# PG3_SHEET1.net
KiCad netlist of a schematic drawn in Altium Designer
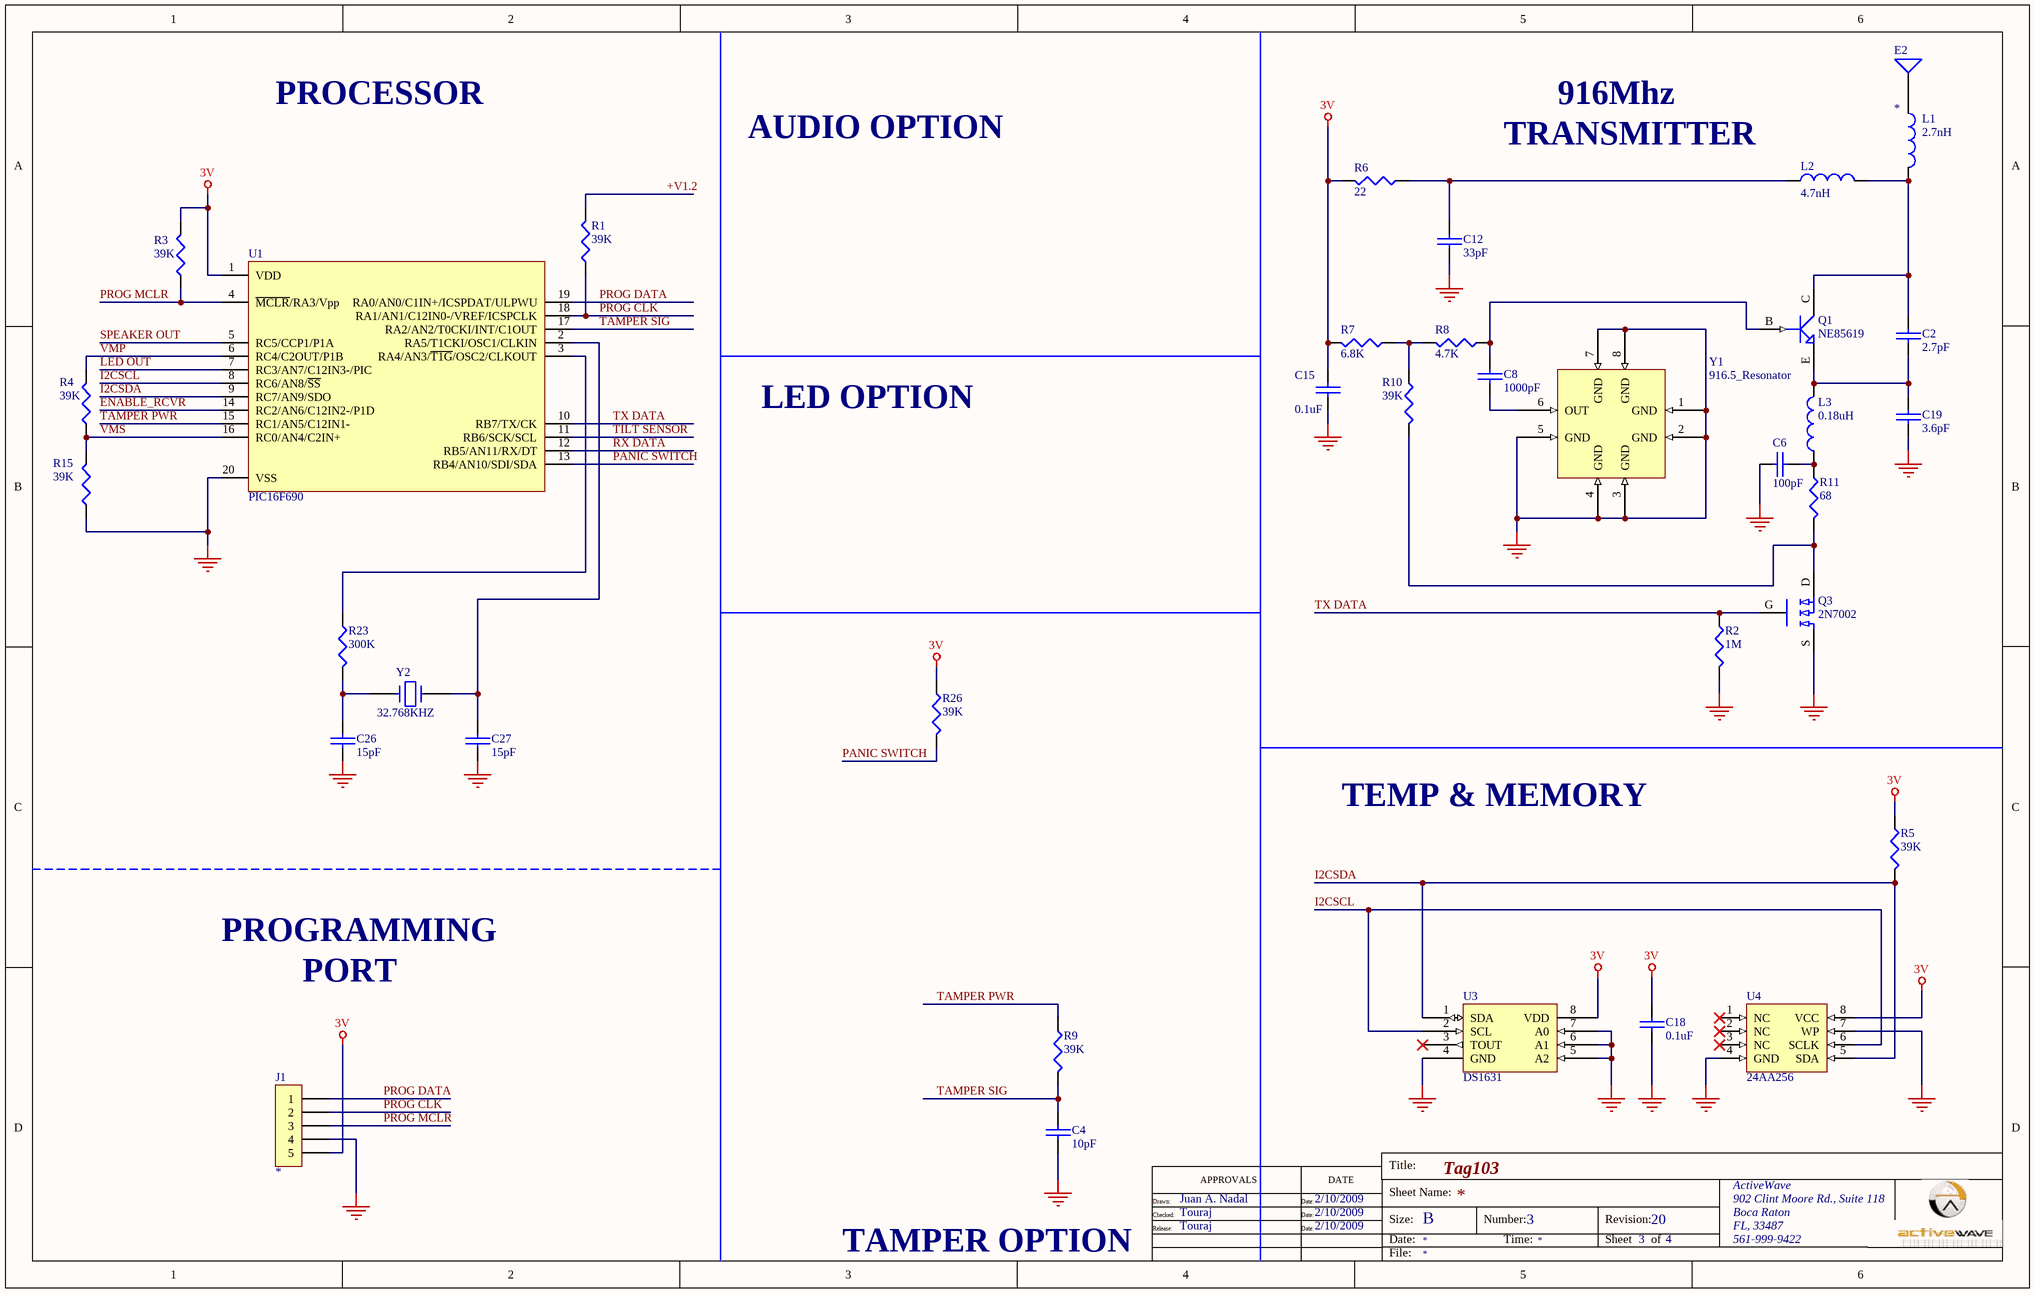
[diagram p0: PG3 SHEET1.schdoc]

(export (version "E")
  (design (tool "Eeschema 10.0.6"))
  (components
    (comp (ref "C2")
      (value "2.7pF")
      (footprint "0603")
      (description "Capacitor")
      (fields (field (name "Comment") "2 PF"))
      (libsource (lib "ActiveWave MasterLib") (part "CAP-0603"))
    )
    (comp (ref "C4")
      (value "10pF")
      (footprint "0603")
      (description "Capacitor")
      (libsource (lib "ActiveWave MasterLib") (part "CAP-0603"))
    )
    (comp (ref "C6")
      (value "100pF")
      (footprint "0603")
      (description "Capacitor")
      (fields (field (name "Comment") "100 pF"))
      (libsource (lib "ActiveWave MasterLib") (part "CAP-0603"))
    )
    (comp (ref "C8")
      (value "1000pF")
      (footprint "0603")
      (description "Capacitor")
      (fields (field (name "Comment") "1000 pF"))
      (libsource (lib "ActiveWave MasterLib") (part "CAP-0603"))
    )
    (comp (ref "C12")
      (value "33pF")
      (footprint "0603")
      (description "Capacitor")
      (fields (field (name "Comment") "33 pF"))
      (libsource (lib "ActiveWave MasterLib") (part "CAP-0603"))
    )
    (comp (ref "C15")
      (value "0.1uF")
      (footprint "0603")
      (description "Capacitor")
      (fields (field (name "Comment") "0.1 uF"))
      (libsource (lib "ActiveWave MasterLib") (part "CAP-0603"))
    )
    (comp (ref "C18")
      (value "0.1uF")
      (footprint "0603")
      (description "Capacitor")
      (fields (field (name "Comment") "0.1 uF"))
      (libsource (lib "ActiveWave MasterLib") (part "CAP-0603"))
    )
    (comp (ref "C19")
      (value "3.6pF")
      (footprint "0603")
      (description "Capacitor")
      (fields (field (name "Comment") "2.7 pF"))
      (libsource (lib "ActiveWave MasterLib") (part "CAP-0603"))
    )
    (comp (ref "C26")
      (value "15pF")
      (footprint "0603")
      (description "Capacitor")
      (libsource (lib "ActiveWave MasterLib") (part "CAP-0603"))
    )
    (comp (ref "C27")
      (value "15pF")
      (footprint "0603")
      (description "Capacitor")
      (libsource (lib "ActiveWave MasterLib") (part "CAP-0603"))
    )
    (comp (ref "E2")
      (value "*")
      (footprint "Antenna1")
      (fields (field (name "PART-VALUE") "*"))
      (libsource (lib "ActiveWave MasterLib") (part "Antenna1"))
    )
    (comp (ref "J1")
      (value "1X5 HEADER")
      (footprint "CONN5")
      (description "Connector")
      (fields (field (name "PART-VALUE") "*"))
      (libsource (lib "ActiveWave MasterLib") (part "CON5"))
    )
    (comp (ref "L1")
      (value "2.7nH")
      (footprint "0603")
      (libsource (lib "ActiveWave MasterLib") (part "INDUCTOR"))
    )
    (comp (ref "L2")
      (value "4.7nH")
      (footprint "0603")
      (fields (field (name "Comment") "10nH"))
      (libsource (lib "ActiveWave MasterLib") (part "INDUCTOR"))
    )
    (comp (ref "L3")
      (value "0.18uH")
      (footprint "0603")
      (libsource (lib "ActiveWave MasterLib") (part "INDUCTOR"))
    )
    (comp (ref "Q1")
      (value "NE85619")
      (footprint "3 PIN ULTRA SUPER MINI MOLD")
      (description "NPN Transistor")
      (libsource (lib "ActiveWave MasterLib") (part "NE85619"))
    )
    (comp (ref "Q3")
      (value "2N7002")
      (footprint "SOT23 FET")
      (libsource (lib "ActiveWave MasterLib") (part "2N7002"))
    )
    (comp (ref "R1")
      (value "39K")
      (footprint "0603")
      (libsource (lib "ActiveWave MasterLib") (part "RES-0603"))
    )
    (comp (ref "R2")
      (value "1M")
      (fields (field (name "Comment") "1 M"))
      (libsource (lib "ActiveWave MasterLib") (part "RES-0402"))
    )
    (comp (ref "R3")
      (value "39K")
      (footprint "0603")
      (libsource (lib "ActiveWave MasterLib") (part "RES-0603"))
    )
    (comp (ref "R4")
      (value "39K")
      (footprint "0603")
      (libsource (lib "ActiveWave MasterLib") (part "RES-0603"))
    )
    (comp (ref "R5")
      (value "39K")
      (footprint "0603")
      (libsource (lib "ActiveWave MasterLib") (part "RES-0603"))
    )
    (comp (ref "R6") (value "22") (libsource (lib "ActiveWave MasterLib") (part "RES-0402")))
    (comp (ref "R7") (value "6.8K") (libsource (lib "ActiveWave MasterLib") (part "RES-0402")))
    (comp (ref "R8")
      (value "4.7K")
      (fields (field (name "Comment") "4.7 K"))
      (libsource (lib "ActiveWave MasterLib") (part "RES-0402"))
    )
    (comp (ref "R9")
      (value "39K")
      (footprint "0603")
      (libsource (lib "ActiveWave MasterLib") (part "RES-0603"))
    )
    (comp (ref "R10")
      (value "39K")
      (footprint "0603")
      (libsource (lib "ActiveWave MasterLib") (part "RES-0603"))
    )
    (comp (ref "R11") (value "68") (libsource (lib "ActiveWave MasterLib") (part "RES-0402")))
    (comp (ref "R15")
      (value "39K")
      (footprint "0603")
      (libsource (lib "ActiveWave MasterLib") (part "RES-0603"))
    )
    (comp (ref "R23")
      (value "300K")
      (footprint "0603")
      (libsource (lib "ActiveWave MasterLib") (part "RES-0603"))
    )
    (comp (ref "R26")
      (value "39K")
      (footprint "0603")
      (fields (field (name "Comment") "4.7M"))
      (libsource (lib "ActiveWave MasterLib") (part "RES-0603"))
    )
    (comp (ref "U1")
      (value "PIC16F690")
      (footprint "SSOP20 WIDE")
      (libsource (lib "ActiveWave MasterLib") (part "PIC16F690"))
    )
    (comp (ref "U3")
      (value "DS1631")
      (footprint "SO8 SMALL")
      (libsource (lib "ActiveWave MasterLib") (part "DS1631"))
    )
    (comp (ref "U4")
      (value "24AA256")
      (footprint "SO8")
      (libsource (lib "ActiveWave MasterLib") (part "24AA256"))
    )
    (comp (ref "Y1")
      (value "916.5_Resonator")
      (footprint "RESONATOR")
      (libsource (lib "ActiveWave MasterLib") (part "RESONATOR"))
    )
    (comp (ref "Y2")
      (value "32.768KHZ")
      (footprint "CRYSTAL ABRACON ABS07")
      (description "Crystal")
      (fields (field (name "Comment") "32.768KHZ CRYSTAL"))
      (libsource (lib "ActiveWave MasterLib") (part "CRYSTAL"))
    )
  )
  (nets
    (net (code "1") (name "/+V1.2") (class "Default")
      (node (ref "R1") (pin "2") (pinfunction "2_2") (pintype "passive"))
    )
    (net (code "2") (name "/ENABLE_RCVR") (class "Default")
      (node (ref "U1") (pin "14") (pinfunction "RC2/AN6/C12IN2-/P1D_14") (pintype "passive"))
    )
    (net (code "3") (name "/I2CSCL") (class "Default")
      (node (ref "U1") (pin "8") (pinfunction "RC6/AN8/~{SS}_8") (pintype "passive"))
      (node (ref "U3") (pin "2") (pinfunction "SCL_2") (pintype "input"))
      (node (ref "U4") (pin "6") (pinfunction "SCLK_6") (pintype "input"))
    )
    (net (code "4") (name "/I2CSDA") (class "Default")
      (node (ref "R5") (pin "2") (pinfunction "2_2") (pintype "passive"))
      (node (ref "U1") (pin "9") (pinfunction "RC7/AN9/SDO_9") (pintype "passive"))
      (node (ref "U3") (pin "1") (pinfunction "SDA_1") (pintype "bidirectional"))
      (node (ref "U4") (pin "5") (pinfunction "SDA_5") (pintype "input"))
    )
    (net (code "5") (name "/LED OUT") (class "Default")
      (node (ref "U1") (pin "7") (pinfunction "RC3/AN7/C12IN3-/PIC_7") (pintype "passive"))
    )
    (net (code "6") (name "/PANIC SWITCH") (class "Default")
      (node (ref "R26") (pin "2") (pinfunction "2_2") (pintype "passive"))
      (node (ref "U1") (pin "13") (pinfunction "RB4/AN10/SDI/SDA_13") (pintype "passive"))
    )
    (net (code "7") (name "/PROG CLK") (class "Default")
      (node (ref "J1") (pin "2") (pinfunction "2_2") (pintype "passive"))
      (node (ref "R1") (pin "1") (pinfunction "1_1") (pintype "passive"))
      (node (ref "U1") (pin "18") (pinfunction "RA1/AN1/C12IN0-/VREF/ICSPCLK_18") (pintype "passive"))
    )
    (net (code "8") (name "/PROG DATA") (class "Default")
      (node (ref "J1") (pin "1") (pinfunction "1_1") (pintype "passive"))
      (node (ref "U1") (pin "19") (pinfunction "RA0/AN0/C1IN+/ICSPDAT/ULPWU_19") (pintype "passive"))
    )
    (net (code "9") (name "/PROG MCLR") (class "Default")
      (node (ref "J1") (pin "3") (pinfunction "3_3") (pintype "passive"))
      (node (ref "R3") (pin "1") (pinfunction "1_1") (pintype "passive"))
      (node (ref "U1") (pin "4") (pinfunction "~{MCLR}/RA3/Vpp_4") (pintype "passive"))
    )
    (net (code "10") (name "/RX DATA") (class "Default")
      (node (ref "U1") (pin "12") (pinfunction "RB5/AN11/RX/DT_12") (pintype "passive"))
    )
    (net (code "11") (name "/SPEAKER OUT") (class "Default")
      (node (ref "U1") (pin "5") (pinfunction "RC5/CCP1/P1A_5") (pintype "passive"))
    )
    (net (code "12") (name "/TAMPER PWR") (class "Default")
      (node (ref "R9") (pin "1") (pinfunction "1_1") (pintype "passive"))
      (node (ref "U1") (pin "15") (pinfunction "RC1/AN5/C12IN1-_15") (pintype "passive"))
    )
    (net (code "13") (name "/TAMPER SIG") (class "Default")
      (node (ref "C4") (pin "1") (pinfunction "1_1") (pintype "passive"))
      (node (ref "R9") (pin "2") (pinfunction "2_2") (pintype "passive"))
      (node (ref "U1") (pin "17") (pinfunction "RA2/AN2/T0CKI/INT/C1OUT_17") (pintype "passive"))
    )
    (net (code "14") (name "/TILT SENSOR") (class "Default")
      (node (ref "U1") (pin "11") (pinfunction "RB6/SCK/SCL_11") (pintype "passive"))
    )
    (net (code "15") (name "/TX DATA") (class "Default")
      (node (ref "Q3") (pin "G") (pinfunction "G_G") (pintype "passive"))
      (node (ref "R2") (pin "1") (pinfunction "1_1") (pintype "passive"))
      (node (ref "U1") (pin "10") (pinfunction "RB7/TX/CK_10") (pintype "passive"))
    )
    (net (code "16") (name "/VMP") (class "Default")
      (node (ref "R4") (pin "2") (pinfunction "2_2") (pintype "passive"))
      (node (ref "U1") (pin "6") (pinfunction "RC4/C2OUT/P1B_6") (pintype "passive"))
    )
    (net (code "17") (name "/VMS") (class "Default")
      (node (ref "R15") (pin "2") (pinfunction "2_2") (pintype "passive"))
      (node (ref "R4") (pin "1") (pinfunction "1_1") (pintype "passive"))
      (node (ref "U1") (pin "16") (pinfunction "RC0/AN4/C2IN+_16") (pintype "passive"))
    )
    (net (code "18") (name "3V") (class "Default")
      (node (ref "C15") (pin "1") (pinfunction "1_1") (pintype "passive"))
      (node (ref "C18") (pin "1") (pinfunction "1_1") (pintype "passive"))
      (node (ref "J1") (pin "5") (pinfunction "5_5") (pintype "passive"))
      (node (ref "R26") (pin "1") (pinfunction "1_1") (pintype "passive"))
      (node (ref "R3") (pin "2") (pinfunction "2_2") (pintype "passive"))
      (node (ref "R5") (pin "1") (pinfunction "1_1") (pintype "passive"))
      (node (ref "R6") (pin "2") (pinfunction "2_2") (pintype "passive"))
      (node (ref "R7") (pin "2") (pinfunction "2_2") (pintype "passive"))
      (node (ref "U1") (pin "1") (pinfunction "VDD_1") (pintype "passive"))
      (node (ref "U3") (pin "8") (pinfunction "VDD_8") (pintype "power_in"))
      (node (ref "U4") (pin "8") (pinfunction "VCC_8") (pintype "input"))
    )
    (net (code "19") (name "GND") (class "Default")
      (node (ref "C12") (pin "2") (pinfunction "2_2") (pintype "passive"))
      (node (ref "C15") (pin "2") (pinfunction "2_2") (pintype "passive"))
      (node (ref "C18") (pin "2") (pinfunction "2_2") (pintype "passive"))
      (node (ref "C19") (pin "2") (pinfunction "2_2") (pintype "passive"))
      (node (ref "C26") (pin "2") (pinfunction "2_2") (pintype "passive"))
      (node (ref "C27") (pin "2") (pinfunction "2_2") (pintype "passive"))
      (node (ref "C4") (pin "2") (pinfunction "2_2") (pintype "passive"))
      (node (ref "C6") (pin "2") (pinfunction "2_2") (pintype "passive"))
      (node (ref "J1") (pin "4") (pinfunction "4_4") (pintype "passive"))
      (node (ref "Q3") (pin "S") (pinfunction "S_S") (pintype "passive"))
      (node (ref "R15") (pin "1") (pinfunction "1_1") (pintype "passive"))
      (node (ref "R2") (pin "2") (pinfunction "2_2") (pintype "passive"))
      (node (ref "U1") (pin "20") (pinfunction "VSS_20") (pintype "passive"))
      (node (ref "U3") (pin "4") (pinfunction "GND_4") (pintype "power_in"))
      (node (ref "U3") (pin "5") (pinfunction "A2_5") (pintype "input"))
      (node (ref "U3") (pin "6") (pinfunction "A1_6") (pintype "input"))
      (node (ref "U3") (pin "7") (pinfunction "A0_7") (pintype "input"))
      (node (ref "U4") (pin "4") (pinfunction "GND_4") (pintype "input"))
      (node (ref "U4") (pin "7") (pinfunction "WP_7") (pintype "input"))
      (node (ref "Y1") (pin "1") (pinfunction "GND_1") (pintype "input"))
      (node (ref "Y1") (pin "2") (pinfunction "GND_2") (pintype "input"))
      (node (ref "Y1") (pin "3") (pinfunction "GND_3") (pintype "input"))
      (node (ref "Y1") (pin "4") (pinfunction "GND_4") (pintype "input"))
      (node (ref "Y1") (pin "5") (pinfunction "GND_5") (pintype "input"))
      (node (ref "Y1") (pin "7") (pinfunction "GND_7") (pintype "input"))
      (node (ref "Y1") (pin "8") (pinfunction "GND_8") (pintype "input"))
    )
    (net (code "20") (name "Net-(C2-Pad1)") (class "Default")
      (node (ref "C2") (pin "1") (pinfunction "1_1") (pintype "passive"))
      (node (ref "L1") (pin "2") (pinfunction "2_2") (pintype "passive"))
      (node (ref "L2") (pin "2") (pinfunction "2_2") (pintype "passive"))
      (node (ref "Q1") (pin "C") (pinfunction "C_C") (pintype "passive"))
    )
    (net (code "21") (name "Net-(C6-Pad1)") (class "Default")
      (node (ref "C6") (pin "1") (pinfunction "1_1") (pintype "passive"))
      (node (ref "L3") (pin "1") (pinfunction "1_1") (pintype "passive"))
      (node (ref "R11") (pin "1") (pinfunction "1_1") (pintype "passive"))
    )
    (net (code "22") (name "Net-(C8-Pad1)") (class "Default")
      (node (ref "C8") (pin "1") (pinfunction "1_1") (pintype "passive"))
      (node (ref "Q1") (pin "B") (pinfunction "B_B") (pintype "input"))
      (node (ref "R8") (pin "1") (pinfunction "1_1") (pintype "passive"))
    )
    (net (code "23") (name "Net-(C12-Pad1)") (class "Default")
      (node (ref "C12") (pin "1") (pinfunction "1_1") (pintype "passive"))
      (node (ref "L2") (pin "1") (pinfunction "1_1") (pintype "passive"))
      (node (ref "R6") (pin "1") (pinfunction "1_1") (pintype "passive"))
    )
    (net (code "24") (name "Net-(C19-Pad1)") (class "Default")
      (node (ref "C19") (pin "1") (pinfunction "1_1") (pintype "passive"))
      (node (ref "C2") (pin "2") (pinfunction "2_2") (pintype "passive"))
      (node (ref "L3") (pin "2") (pinfunction "2_2") (pintype "passive"))
      (node (ref "Q1") (pin "E") (pinfunction "E_E") (pintype "passive"))
    )
    (net (code "25") (name "Net-(C26-Pad1)") (class "Default")
      (node (ref "C26") (pin "1") (pinfunction "1_1") (pintype "passive"))
      (node (ref "R23") (pin "2") (pinfunction "2_2") (pintype "passive"))
      (node (ref "Y2") (pin "1") (pinfunction "1_1") (pintype "passive"))
    )
    (net (code "26") (name "Net-(E2-Pad1)") (class "Default")
      (node (ref "E2") (pin "1") (pinfunction "1_1") (pintype "passive"))
      (node (ref "L1") (pin "1") (pinfunction "1_1") (pintype "passive"))
    )
    (net (code "27") (name "Net-(Q3-PadD)") (class "Default")
      (node (ref "Q3") (pin "D") (pinfunction "D_D") (pintype "passive"))
      (node (ref "R10") (pin "2") (pinfunction "2_2") (pintype "passive"))
      (node (ref "R11") (pin "2") (pinfunction "2_2") (pintype "passive"))
    )
    (net (code "28") (name "Net-(R10-Pad1)") (class "Default")
      (node (ref "R10") (pin "1") (pinfunction "1_1") (pintype "passive"))
      (node (ref "R7") (pin "1") (pinfunction "1_1") (pintype "passive"))
      (node (ref "R8") (pin "2") (pinfunction "2_2") (pintype "passive"))
    )
    (net (code "29") (name "Net-(U1-RA4{slash}AN3{slash}~{T1G}{slash}OSC2{slash}CLKOUT)") (class "Default")
      (node (ref "R23") (pin "1") (pinfunction "1_1") (pintype "passive"))
      (node (ref "U1") (pin "3") (pinfunction "RA4/AN3/~{T1G}/OSC2/CLKOUT_3") (pintype "passive"))
    )
    (net (code "30") (name "Net-(U1-RA5{slash}T1CKI{slash}OSC1{slash}CLKIN)") (class "Default")
      (node (ref "C27") (pin "1") (pinfunction "1_1") (pintype "passive"))
      (node (ref "U1") (pin "2") (pinfunction "RA5/T1CKI/OSC1/CLKIN_2") (pintype "passive"))
      (node (ref "Y2") (pin "2") (pinfunction "2_2") (pintype "passive"))
    )
    (net (code "31") (name "Net-(Y1-OUT)") (class "Default")
      (node (ref "C8") (pin "2") (pinfunction "2_2") (pintype "passive"))
      (node (ref "Y1") (pin "6") (pinfunction "OUT_6") (pintype "input"))
    )
    (net (code "32") (name "unconnected-(U3-TOUT-Pad3)") (class "Default")
      (node (ref "U3") (pin "3") (pinfunction "TOUT_3") (pintype "output+no_connect"))
    )
    (net (code "33") (name "unconnected-(U4-NC-Pad1)") (class "Default")
      (node (ref "U4") (pin "1") (pinfunction "NC_1") (pintype "input+no_connect"))
    )
    (net (code "34") (name "unconnected-(U4-NC-Pad2)") (class "Default")
      (node (ref "U4") (pin "2") (pinfunction "NC_2") (pintype "input+no_connect"))
    )
    (net (code "35") (name "unconnected-(U4-NC-Pad3)") (class "Default")
      (node (ref "U4") (pin "3") (pinfunction "NC_3") (pintype "input+no_connect"))
    )
  )
)
